# robot_dripper.net
KiCad netlist of a schematic drawn in EAGLE
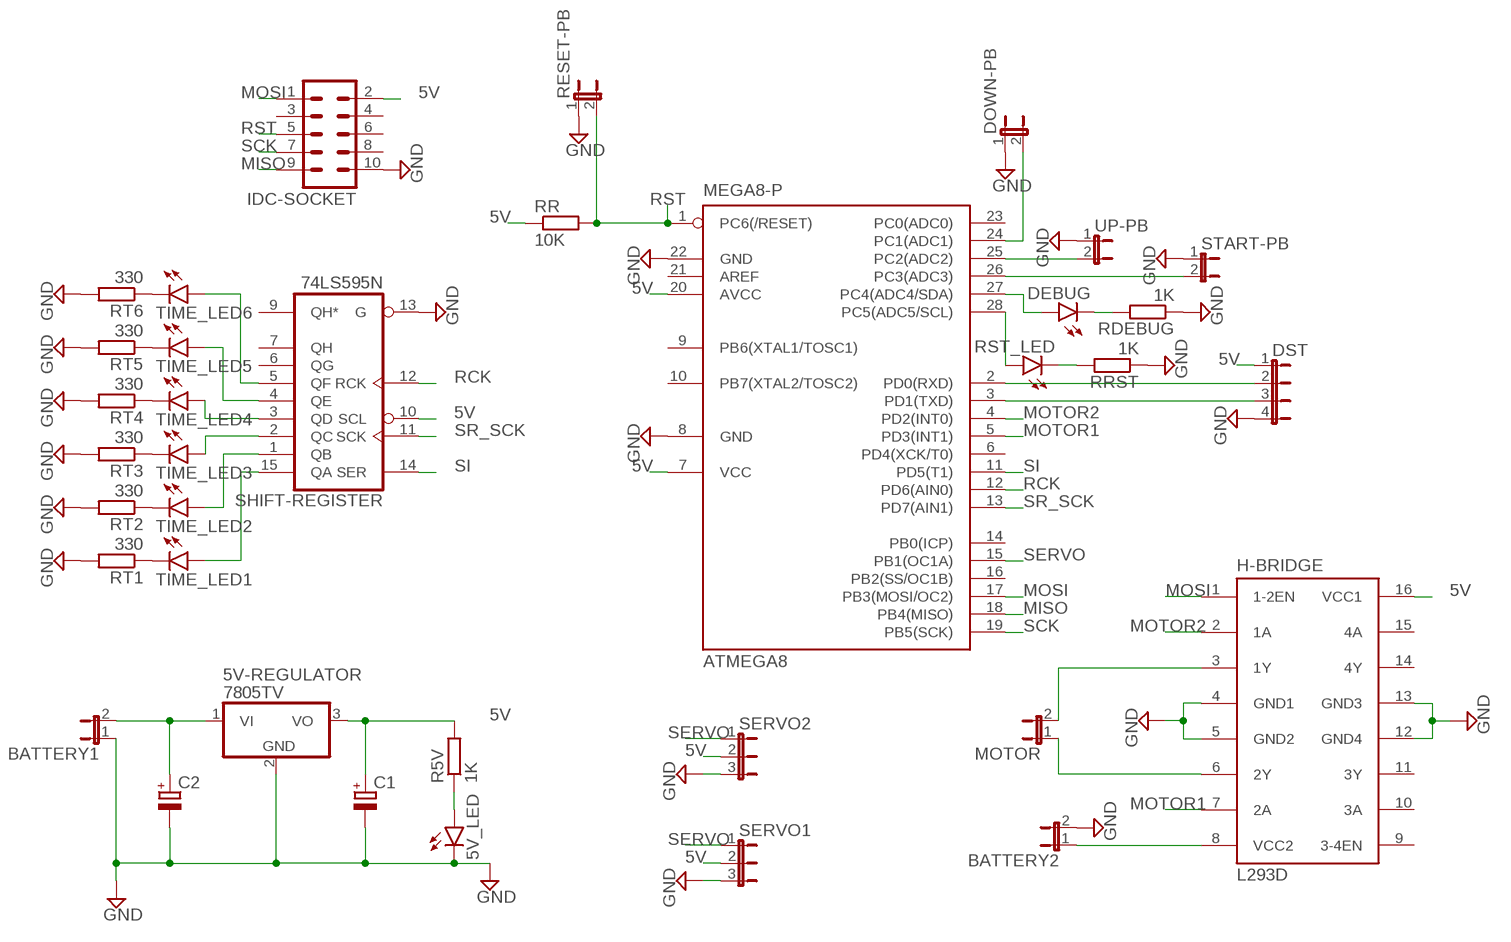
[diagram p0: schematic, sheet 1]

(export (version "E")
  (design (tool "Eeschema 10.0.6"))
  (components
    (comp (ref "5V-REGULATOR")
      (value "7805TV")
      (footprint "eagle-import:TO220V")
      (libsource (lib "eagle-import") (part "78TV05"))
    )
    (comp (ref "5V_LED")
      (value "LED5MM")
      (footprint "eagle-import:LED5MM")
      (libsource (lib "eagle-import") (part "LED5MM"))
    )
    (comp (ref "ATMEGA8")
      (value "MEGA8-P")
      (footprint "eagle-import:DIL28-3")
      (libsource (lib "eagle-import") (part "MEGA8-P"))
    )
    (comp (ref "BATTERY1")
      (value "JP1E")
      (footprint "eagle-import:JP1")
      (libsource (lib "eagle-import") (part "JP1E"))
    )
    (comp (ref "BATTERY2")
      (value "JP1E")
      (footprint "eagle-import:JP1")
      (libsource (lib "eagle-import") (part "JP1E"))
    )
    (comp (ref "C1")
      (value "CPOL-EUE5-10.5")
      (footprint "eagle-import:E5-10,5")
      (libsource (lib "eagle-import") (part "CPOL-EUE5-10.5"))
    )
    (comp (ref "C2")
      (value "CPOL-EUE5-10.5")
      (footprint "eagle-import:E5-10,5")
      (libsource (lib "eagle-import") (part "CPOL-EUE5-10.5"))
    )
    (comp (ref "DEBUG")
      (value "LED5MM")
      (footprint "eagle-import:LED5MM")
      (libsource (lib "eagle-import") (part "LED5MM"))
    )
    (comp (ref "DOWN-PB")
      (value "JP1E")
      (footprint "eagle-import:JP1")
      (libsource (lib "eagle-import") (part "JP1E"))
    )
    (comp (ref "DST")
      (value "JP4E")
      (footprint "eagle-import:JP4")
      (libsource (lib "eagle-import") (part "JP4E"))
    )
    (comp (ref "H-BRIDGE")
      (value "L293D")
      (footprint "eagle-import:DIL16")
      (libsource (lib "eagle-import") (part "L293D"))
    )
    (comp (ref "IDC-SOCKET")
      (value "ML10")
      (footprint "eagle-import:ML10")
      (libsource (lib "eagle-import") (part "ML10"))
    )
    (comp (ref "MOTOR")
      (value "JP1E")
      (footprint "eagle-import:JP1")
      (libsource (lib "eagle-import") (part "JP1E"))
    )
    (comp (ref "R5V")
      (value "1K")
      (footprint "eagle-import:0207_10")
      (libsource (lib "eagle-import") (part "R-EU_0207/10"))
    )
    (comp (ref "RDEBUG")
      (value "1K")
      (footprint "eagle-import:0207_10")
      (libsource (lib "eagle-import") (part "R-EU_0207/10"))
    )
    (comp (ref "RESET-PB")
      (value "JP1E")
      (footprint "eagle-import:JP1")
      (libsource (lib "eagle-import") (part "JP1E"))
    )
    (comp (ref "RR")
      (value "10K")
      (footprint "eagle-import:0207_10")
      (libsource (lib "eagle-import") (part "R-EU_0207/10"))
    )
    (comp (ref "RRST")
      (value "1K")
      (footprint "eagle-import:0207_10")
      (libsource (lib "eagle-import") (part "R-EU_0207/10"))
    )
    (comp (ref "RST_LED")
      (value "LED5MM")
      (footprint "eagle-import:LED5MM")
      (libsource (lib "eagle-import") (part "LED5MM"))
    )
    (comp (ref "RT1")
      (value "330")
      (footprint "eagle-import:0207_10")
      (libsource (lib "eagle-import") (part "R-EU_0207/10"))
    )
    (comp (ref "RT2")
      (value "330")
      (footprint "eagle-import:0207_10")
      (libsource (lib "eagle-import") (part "R-EU_0207/10"))
    )
    (comp (ref "RT3")
      (value "330")
      (footprint "eagle-import:0207_10")
      (libsource (lib "eagle-import") (part "R-EU_0207/10"))
    )
    (comp (ref "RT4")
      (value "330")
      (footprint "eagle-import:0207_10")
      (libsource (lib "eagle-import") (part "R-EU_0207/10"))
    )
    (comp (ref "RT5")
      (value "330")
      (footprint "eagle-import:0207_10")
      (libsource (lib "eagle-import") (part "R-EU_0207/10"))
    )
    (comp (ref "RT6")
      (value "330")
      (footprint "eagle-import:0207_10")
      (libsource (lib "eagle-import") (part "R-EU_0207/10"))
    )
    (comp (ref "SERVO1")
      (value "JP2E")
      (footprint "eagle-import:JP2")
      (libsource (lib "eagle-import") (part "JP2E"))
    )
    (comp (ref "SERVO2")
      (value "JP2E")
      (footprint "eagle-import:JP2")
      (libsource (lib "eagle-import") (part "JP2E"))
    )
    (comp (ref "SHIFT-REGISTER")
      (value "74LS595N")
      (footprint "eagle-import:DIL16")
      (libsource (lib "eagle-import") (part "74595NLS"))
    )
    (comp (ref "START-PB")
      (value "JP1E")
      (footprint "eagle-import:JP1")
      (libsource (lib "eagle-import") (part "JP1E"))
    )
    (comp (ref "TIME_LED1")
      (value "LED5MM")
      (footprint "eagle-import:LED5MM")
      (libsource (lib "eagle-import") (part "LED5MM"))
    )
    (comp (ref "TIME_LED2")
      (value "LED5MM")
      (footprint "eagle-import:LED5MM")
      (libsource (lib "eagle-import") (part "LED5MM"))
    )
    (comp (ref "TIME_LED3")
      (value "LED5MM")
      (footprint "eagle-import:LED5MM")
      (libsource (lib "eagle-import") (part "LED5MM"))
    )
    (comp (ref "TIME_LED4")
      (value "LED5MM")
      (footprint "eagle-import:LED5MM")
      (libsource (lib "eagle-import") (part "LED5MM"))
    )
    (comp (ref "TIME_LED5")
      (value "LED5MM")
      (footprint "eagle-import:LED5MM")
      (libsource (lib "eagle-import") (part "LED5MM"))
    )
    (comp (ref "TIME_LED6")
      (value "LED5MM")
      (footprint "eagle-import:LED5MM")
      (libsource (lib "eagle-import") (part "LED5MM"))
    )
    (comp (ref "UP-PB")
      (value "JP1E")
      (footprint "eagle-import:JP1")
      (libsource (lib "eagle-import") (part "JP1E"))
    )
  )
  (nets
    (net (code "1") (name "/5V") (class "Default")
      (node (ref "5V-REGULATOR") (pin "3") (pinfunction "VO_3") (pintype "passive"))
      (node (ref "ATMEGA8") (pin "20") (pinfunction "AVCC_20") (pintype "power_in"))
      (node (ref "ATMEGA8") (pin "7") (pinfunction "VCC_7") (pintype "power_in"))
      (node (ref "C1") (pin "+") (pinfunction "+_+") (pintype "passive"))
      (node (ref "DST") (pin "1") (pinfunction "1_1") (pintype "passive"))
      (node (ref "H-BRIDGE") (pin "16") (pinfunction "VCC1_16") (pintype "power_in"))
      (node (ref "IDC-SOCKET") (pin "2") (pinfunction "2_2") (pintype "passive"))
      (node (ref "R5V") (pin "2") (pinfunction "2_2") (pintype "passive"))
      (node (ref "RR") (pin "1") (pinfunction "1_1") (pintype "passive"))
      (node (ref "SERVO1") (pin "2") (pinfunction "2_2") (pintype "passive"))
      (node (ref "SERVO2") (pin "2") (pinfunction "2_2") (pintype "passive"))
      (node (ref "SHIFT-REGISTER") (pin "10") (pinfunction "SCL_10") (pintype "input"))
    )
    (net (code "2") (name "/MISO") (class "Default")
      (node (ref "ATMEGA8") (pin "18") (pinfunction "PB4(MISO)_18") (pintype "bidirectional"))
      (node (ref "IDC-SOCKET") (pin "9") (pinfunction "9_9") (pintype "passive"))
    )
    (net (code "3") (name "/MOSI") (class "Default")
      (node (ref "ATMEGA8") (pin "17") (pinfunction "PB3(MOSI/OC2)_17") (pintype "bidirectional"))
      (node (ref "H-BRIDGE") (pin "1") (pinfunction "1-2EN_1") (pintype "input"))
      (node (ref "IDC-SOCKET") (pin "1") (pinfunction "1_1") (pintype "passive"))
    )
    (net (code "4") (name "/MOTOR1") (class "Default")
      (node (ref "ATMEGA8") (pin "5") (pinfunction "PD3(INT1)_5") (pintype "bidirectional"))
      (node (ref "H-BRIDGE") (pin "7") (pinfunction "2A_7") (pintype "input"))
    )
    (net (code "5") (name "/MOTOR2") (class "Default")
      (node (ref "ATMEGA8") (pin "4") (pinfunction "PD2(INT0)_4") (pintype "bidirectional"))
      (node (ref "H-BRIDGE") (pin "2") (pinfunction "1A_2") (pintype "input"))
    )
    (net (code "6") (name "/RCK") (class "Default")
      (node (ref "ATMEGA8") (pin "12") (pinfunction "PD6(AIN0)_12") (pintype "bidirectional"))
      (node (ref "SHIFT-REGISTER") (pin "12") (pinfunction "RCK_12") (pintype "input"))
    )
    (net (code "7") (name "/RST") (class "Default")
      (node (ref "ATMEGA8") (pin "1") (pinfunction "PC6(/RESET)_1") (pintype "bidirectional"))
      (node (ref "IDC-SOCKET") (pin "5") (pinfunction "5_5") (pintype "passive"))
      (node (ref "RESET-PB") (pin "2") (pinfunction "2_2") (pintype "passive"))
      (node (ref "RR") (pin "2") (pinfunction "2_2") (pintype "passive"))
    )
    (net (code "8") (name "/SCK") (class "Default")
      (node (ref "ATMEGA8") (pin "19") (pinfunction "PB5(SCK)_19") (pintype "bidirectional"))
      (node (ref "IDC-SOCKET") (pin "7") (pinfunction "7_7") (pintype "passive"))
    )
    (net (code "9") (name "/SERVO") (class "Default")
      (node (ref "ATMEGA8") (pin "15") (pinfunction "PB1(OC1A)_15") (pintype "bidirectional"))
      (node (ref "SERVO1") (pin "1") (pinfunction "1_1") (pintype "passive"))
      (node (ref "SERVO2") (pin "1") (pinfunction "1_1") (pintype "passive"))
    )
    (net (code "10") (name "/SI") (class "Default")
      (node (ref "ATMEGA8") (pin "11") (pinfunction "PD5(T1)_11") (pintype "bidirectional"))
      (node (ref "SHIFT-REGISTER") (pin "14") (pinfunction "SER_14") (pintype "input"))
    )
    (net (code "11") (name "/SR_SCK") (class "Default")
      (node (ref "ATMEGA8") (pin "13") (pinfunction "PD7(AIN1)_13") (pintype "bidirectional"))
      (node (ref "SHIFT-REGISTER") (pin "11") (pinfunction "SCK_11") (pintype "input"))
    )
    (net (code "12") (name "GND") (class "Default")
      (node (ref "5V-REGULATOR") (pin "2") (pinfunction "GND_2") (pintype "passive"))
      (node (ref "5V_LED") (pin "K") (pinfunction "C_K") (pintype "passive"))
      (node (ref "ATMEGA8") (pin "22") (pinfunction "GND_22") (pintype "power_in"))
      (node (ref "ATMEGA8") (pin "8") (pinfunction "GND_8") (pintype "power_in"))
      (node (ref "BATTERY1") (pin "1") (pinfunction "1_1") (pintype "passive"))
      (node (ref "BATTERY2") (pin "2") (pinfunction "2_2") (pintype "passive"))
      (node (ref "C1") (pin "-") (pinfunction "-_-") (pintype "passive"))
      (node (ref "C2") (pin "-") (pinfunction "-_-") (pintype "passive"))
      (node (ref "DOWN-PB") (pin "1") (pinfunction "1_1") (pintype "passive"))
      (node (ref "DST") (pin "4") (pinfunction "4_4") (pintype "passive"))
      (node (ref "H-BRIDGE") (pin "12") (pinfunction "GND4_12") (pintype "power_in"))
      (node (ref "H-BRIDGE") (pin "13") (pinfunction "GND3_13") (pintype "power_in"))
      (node (ref "H-BRIDGE") (pin "4") (pinfunction "GND1_4") (pintype "power_in"))
      (node (ref "H-BRIDGE") (pin "5") (pinfunction "GND2_5") (pintype "power_in"))
      (node (ref "IDC-SOCKET") (pin "10") (pinfunction "10_10") (pintype "passive"))
      (node (ref "RDEBUG") (pin "1") (pinfunction "1_1") (pintype "passive"))
      (node (ref "RESET-PB") (pin "1") (pinfunction "1_1") (pintype "passive"))
      (node (ref "RRST") (pin "1") (pinfunction "1_1") (pintype "passive"))
      (node (ref "RT1") (pin "2") (pinfunction "2_2") (pintype "passive"))
      (node (ref "RT2") (pin "2") (pinfunction "2_2") (pintype "passive"))
      (node (ref "RT3") (pin "2") (pinfunction "2_2") (pintype "passive"))
      (node (ref "RT4") (pin "2") (pinfunction "2_2") (pintype "passive"))
      (node (ref "RT5") (pin "2") (pinfunction "2_2") (pintype "passive"))
      (node (ref "RT6") (pin "2") (pinfunction "2_2") (pintype "passive"))
      (node (ref "SERVO1") (pin "3") (pinfunction "3_3") (pintype "passive"))
      (node (ref "SERVO2") (pin "3") (pinfunction "3_3") (pintype "passive"))
      (node (ref "SHIFT-REGISTER") (pin "13") (pinfunction "G_13") (pintype "input"))
      (node (ref "START-PB") (pin "1") (pinfunction "1_1") (pintype "passive"))
      (node (ref "UP-PB") (pin "1") (pinfunction "1_1") (pintype "passive"))
    )
    (net (code "13") (name "Net-(5V-REGULATOR-VI)") (class "Default")
      (node (ref "5V-REGULATOR") (pin "1") (pinfunction "VI_1") (pintype "input"))
      (node (ref "BATTERY1") (pin "2") (pinfunction "2_2") (pintype "passive"))
      (node (ref "C2") (pin "+") (pinfunction "+_+") (pintype "passive"))
    )
    (net (code "14") (name "Net-(5V_LED-PadA)") (class "Default")
      (node (ref "5V_LED") (pin "A") (pinfunction "A_A") (pintype "passive"))
      (node (ref "R5V") (pin "1") (pinfunction "1_1") (pintype "passive"))
    )
    (net (code "15") (name "Net-(ATMEGA8-PC1(ADC1))") (class "Default")
      (node (ref "ATMEGA8") (pin "24") (pinfunction "PC1(ADC1)_24") (pintype "bidirectional"))
      (node (ref "DOWN-PB") (pin "2") (pinfunction "2_2") (pintype "passive"))
    )
    (net (code "16") (name "Net-(ATMEGA8-PC2(ADC2))") (class "Default")
      (node (ref "ATMEGA8") (pin "25") (pinfunction "PC2(ADC2)_25") (pintype "bidirectional"))
      (node (ref "UP-PB") (pin "2") (pinfunction "2_2") (pintype "passive"))
    )
    (net (code "17") (name "Net-(ATMEGA8-PC3(ADC3))") (class "Default")
      (node (ref "ATMEGA8") (pin "26") (pinfunction "PC3(ADC3)_26") (pintype "bidirectional"))
      (node (ref "START-PB") (pin "2") (pinfunction "2_2") (pintype "passive"))
    )
    (net (code "18") (name "Net-(ATMEGA8-PC4(ADC4{slash}SDA))") (class "Default")
      (node (ref "ATMEGA8") (pin "27") (pinfunction "PC4(ADC4/SDA)_27") (pintype "bidirectional"))
      (node (ref "DEBUG") (pin "A") (pinfunction "A_A") (pintype "passive"))
    )
    (net (code "19") (name "Net-(ATMEGA8-PC5(ADC5{slash}SCL))") (class "Default")
      (node (ref "ATMEGA8") (pin "28") (pinfunction "PC5(ADC5/SCL)_28") (pintype "bidirectional"))
      (node (ref "RST_LED") (pin "A") (pinfunction "A_A") (pintype "passive"))
    )
    (net (code "20") (name "Net-(ATMEGA8-PD0(RXD))") (class "Default")
      (node (ref "ATMEGA8") (pin "2") (pinfunction "PD0(RXD)_2") (pintype "bidirectional"))
      (node (ref "DST") (pin "2") (pinfunction "2_2") (pintype "passive"))
    )
    (net (code "21") (name "Net-(ATMEGA8-PD1(TXD))") (class "Default")
      (node (ref "ATMEGA8") (pin "3") (pinfunction "PD1(TXD)_3") (pintype "bidirectional"))
      (node (ref "DST") (pin "3") (pinfunction "3_3") (pintype "passive"))
    )
    (net (code "22") (name "Net-(DEBUG-C)") (class "Default")
      (node (ref "DEBUG") (pin "K") (pinfunction "C_K") (pintype "passive"))
      (node (ref "RDEBUG") (pin "2") (pinfunction "2_2") (pintype "passive"))
    )
    (net (code "23") (name "Net-(H-BRIDGE-1Y)") (class "Default")
      (node (ref "H-BRIDGE") (pin "3") (pinfunction "1Y_3") (pintype "output"))
      (node (ref "MOTOR") (pin "2") (pinfunction "2_2") (pintype "passive"))
    )
    (net (code "24") (name "Net-(H-BRIDGE-2Y)") (class "Default")
      (node (ref "H-BRIDGE") (pin "6") (pinfunction "2Y_6") (pintype "output"))
      (node (ref "MOTOR") (pin "1") (pinfunction "1_1") (pintype "passive"))
    )
    (net (code "25") (name "Net-(H-BRIDGE-VCC2)") (class "Default")
      (node (ref "BATTERY2") (pin "1") (pinfunction "1_1") (pintype "passive"))
      (node (ref "H-BRIDGE") (pin "8") (pinfunction "VCC2_8") (pintype "power_in"))
    )
    (net (code "26") (name "Net-(RST_LED-C)") (class "Default")
      (node (ref "RRST") (pin "2") (pinfunction "2_2") (pintype "passive"))
      (node (ref "RST_LED") (pin "K") (pinfunction "C_K") (pintype "passive"))
    )
    (net (code "27") (name "Net-(SHIFT-REGISTERA-QA)") (class "Default")
      (node (ref "SHIFT-REGISTER") (pin "15") (pinfunction "QA_15") (pintype "tri_state"))
      (node (ref "TIME_LED1") (pin "A") (pinfunction "A_A") (pintype "passive"))
    )
    (net (code "28") (name "Net-(SHIFT-REGISTERA-QB)") (class "Default")
      (node (ref "SHIFT-REGISTER") (pin "1") (pinfunction "QB_1") (pintype "tri_state"))
      (node (ref "TIME_LED2") (pin "A") (pinfunction "A_A") (pintype "passive"))
    )
    (net (code "29") (name "Net-(SHIFT-REGISTERA-QC)") (class "Default")
      (node (ref "SHIFT-REGISTER") (pin "2") (pinfunction "QC_2") (pintype "tri_state"))
      (node (ref "TIME_LED3") (pin "A") (pinfunction "A_A") (pintype "passive"))
    )
    (net (code "30") (name "Net-(SHIFT-REGISTERA-QD)") (class "Default")
      (node (ref "SHIFT-REGISTER") (pin "3") (pinfunction "QD_3") (pintype "tri_state"))
      (node (ref "TIME_LED4") (pin "A") (pinfunction "A_A") (pintype "passive"))
    )
    (net (code "31") (name "Net-(SHIFT-REGISTERA-QE)") (class "Default")
      (node (ref "SHIFT-REGISTER") (pin "4") (pinfunction "QE_4") (pintype "tri_state"))
      (node (ref "TIME_LED5") (pin "A") (pinfunction "A_A") (pintype "passive"))
    )
    (net (code "32") (name "Net-(SHIFT-REGISTERA-QF)") (class "Default")
      (node (ref "SHIFT-REGISTER") (pin "5") (pinfunction "QF_5") (pintype "tri_state"))
      (node (ref "TIME_LED6") (pin "A") (pinfunction "A_A") (pintype "passive"))
    )
    (net (code "33") (name "Net-(TIME_LED1-C)") (class "Default")
      (node (ref "RT1") (pin "1") (pinfunction "1_1") (pintype "passive"))
      (node (ref "TIME_LED1") (pin "K") (pinfunction "C_K") (pintype "passive"))
    )
    (net (code "34") (name "Net-(TIME_LED2-C)") (class "Default")
      (node (ref "RT2") (pin "1") (pinfunction "1_1") (pintype "passive"))
      (node (ref "TIME_LED2") (pin "K") (pinfunction "C_K") (pintype "passive"))
    )
    (net (code "35") (name "Net-(TIME_LED3-C)") (class "Default")
      (node (ref "RT3") (pin "1") (pinfunction "1_1") (pintype "passive"))
      (node (ref "TIME_LED3") (pin "K") (pinfunction "C_K") (pintype "passive"))
    )
    (net (code "36") (name "Net-(TIME_LED4-C)") (class "Default")
      (node (ref "RT4") (pin "1") (pinfunction "1_1") (pintype "passive"))
      (node (ref "TIME_LED4") (pin "K") (pinfunction "C_K") (pintype "passive"))
    )
    (net (code "37") (name "Net-(TIME_LED5-C)") (class "Default")
      (node (ref "RT5") (pin "1") (pinfunction "1_1") (pintype "passive"))
      (node (ref "TIME_LED5") (pin "K") (pinfunction "C_K") (pintype "passive"))
    )
    (net (code "38") (name "Net-(TIME_LED6-C)") (class "Default")
      (node (ref "RT6") (pin "1") (pinfunction "1_1") (pintype "passive"))
      (node (ref "TIME_LED6") (pin "K") (pinfunction "C_K") (pintype "passive"))
    )
    (net (code "39") (name "unconnected-(ATMEGA8-AREF-Pad21)") (class "Default")
      (node (ref "ATMEGA8") (pin "21") (pinfunction "AREF_21") (pintype "passive"))
    )
    (net (code "40") (name "unconnected-(ATMEGA8-PB0(ICP)-Pad14)") (class "Default")
      (node (ref "ATMEGA8") (pin "14") (pinfunction "PB0(ICP)_14") (pintype "bidirectional"))
    )
    (net (code "41") (name "unconnected-(ATMEGA8-PB2(SS{slash}OC1B)-Pad16)") (class "Default")
      (node (ref "ATMEGA8") (pin "16") (pinfunction "PB2(SS/OC1B)_16") (pintype "bidirectional"))
    )
    (net (code "42") (name "unconnected-(ATMEGA8-PB6(XTAL1{slash}TOSC1)-Pad9)") (class "Default")
      (node (ref "ATMEGA8") (pin "9") (pinfunction "PB6(XTAL1/TOSC1)_9") (pintype "bidirectional"))
    )
    (net (code "43") (name "unconnected-(ATMEGA8-PB7(XTAL2{slash}TOSC2)-Pad10)") (class "Default")
      (node (ref "ATMEGA8") (pin "10") (pinfunction "PB7(XTAL2/TOSC2)_10") (pintype "bidirectional"))
    )
    (net (code "44") (name "unconnected-(ATMEGA8-PC0(ADC0)-Pad23)") (class "Default")
      (node (ref "ATMEGA8") (pin "23") (pinfunction "PC0(ADC0)_23") (pintype "bidirectional"))
    )
    (net (code "45") (name "unconnected-(ATMEGA8-PD4(XCK{slash}T0)-Pad6)") (class "Default")
      (node (ref "ATMEGA8") (pin "6") (pinfunction "PD4(XCK/T0)_6") (pintype "bidirectional"))
    )
    (net (code "46") (name "unconnected-(H-BRIDGE-3-4EN-Pad9)") (class "Default")
      (node (ref "H-BRIDGE") (pin "9") (pinfunction "3-4EN_9") (pintype "input"))
    )
    (net (code "47") (name "unconnected-(H-BRIDGE-3A-Pad10)") (class "Default")
      (node (ref "H-BRIDGE") (pin "10") (pinfunction "3A_10") (pintype "input"))
    )
    (net (code "48") (name "unconnected-(H-BRIDGE-3Y-Pad11)") (class "Default")
      (node (ref "H-BRIDGE") (pin "11") (pinfunction "3Y_11") (pintype "output"))
    )
    (net (code "49") (name "unconnected-(H-BRIDGE-4A-Pad15)") (class "Default")
      (node (ref "H-BRIDGE") (pin "15") (pinfunction "4A_15") (pintype "input"))
    )
    (net (code "50") (name "unconnected-(H-BRIDGE-4Y-Pad14)") (class "Default")
      (node (ref "H-BRIDGE") (pin "14") (pinfunction "4Y_14") (pintype "output"))
    )
    (net (code "51") (name "unconnected-(IDC-SOCKET-Pad3)") (class "Default")
      (node (ref "IDC-SOCKET") (pin "3") (pinfunction "3_3") (pintype "passive"))
    )
    (net (code "52") (name "unconnected-(IDC-SOCKET-Pad4)") (class "Default")
      (node (ref "IDC-SOCKET") (pin "4") (pinfunction "4_4") (pintype "passive"))
    )
    (net (code "53") (name "unconnected-(IDC-SOCKET-Pad6)") (class "Default")
      (node (ref "IDC-SOCKET") (pin "6") (pinfunction "6_6") (pintype "passive"))
    )
    (net (code "54") (name "unconnected-(IDC-SOCKET-Pad8)") (class "Default")
      (node (ref "IDC-SOCKET") (pin "8") (pinfunction "8_8") (pintype "passive"))
    )
    (net (code "55") (name "unconnected-(SHIFT-REGISTERA-QG-Pad6)") (class "Default")
      (node (ref "SHIFT-REGISTER") (pin "6") (pinfunction "QG_6") (pintype "tri_state"))
    )
    (net (code "56") (name "unconnected-(SHIFT-REGISTERA-QH*-Pad9)") (class "Default")
      (node (ref "SHIFT-REGISTER") (pin "9") (pinfunction "QH*_9") (pintype "tri_state"))
    )
    (net (code "57") (name "unconnected-(SHIFT-REGISTERA-QH-Pad7)") (class "Default")
      (node (ref "SHIFT-REGISTER") (pin "7") (pinfunction "QH_7") (pintype "tri_state"))
    )
  )
)
